# ArudinoShield.net
KiCad netlist of a schematic drawn in EAGLE
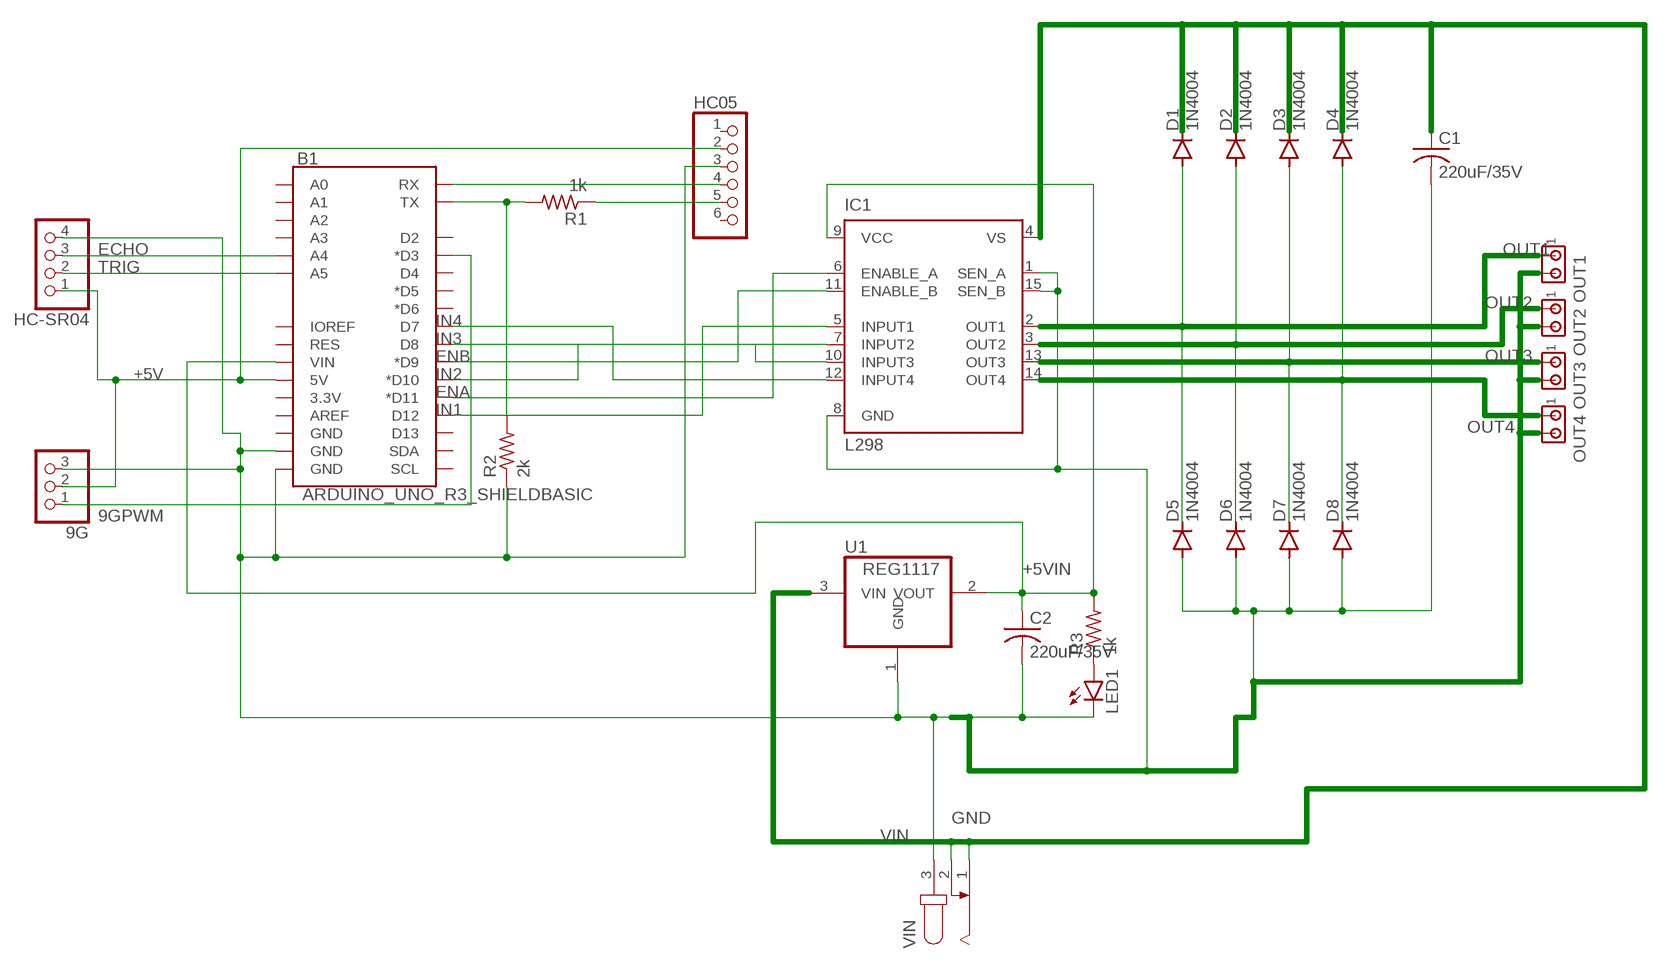
[diagram p0: schematic, sheet 1]

(export (version "E")
  (design (tool "Eeschema 10.0.6"))
  (components
    (comp (ref "9G")
      (value "PINHD-1X3")
      (footprint "eagle-import:1X03")
      (libsource (lib "eagle-import") (part "PINHD-1X3"))
    )
    (comp (ref "B1")
      (value "ARDUINO_UNO_R3_SHIELDBASIC")
      (footprint "eagle-import:UNO_R3_SHIELD")
      (libsource (lib "eagle-import") (part "ARDUINO_UNO_R3_SHIELDBASIC"))
    )
    (comp (ref "C1")
      (value "220uF/35V")
      (footprint "eagle-import:C050-024X044")
      (libsource (lib "eagle-import") (part "C-US050-024X044"))
    )
    (comp (ref "C2")
      (value "220uF/35V")
      (footprint "eagle-import:C050-024X044")
      (libsource (lib "eagle-import") (part "C-US050-024X044"))
    )
    (comp (ref "D1")
      (value "1N4004")
      (footprint "eagle-import:DO41-10")
      (libsource (lib "eagle-import") (part "1N4004"))
    )
    (comp (ref "D2")
      (value "1N4004")
      (footprint "eagle-import:DO41-10")
      (libsource (lib "eagle-import") (part "1N4004"))
    )
    (comp (ref "D3")
      (value "1N4004")
      (footprint "eagle-import:DO41-10")
      (libsource (lib "eagle-import") (part "1N4004"))
    )
    (comp (ref "D4")
      (value "1N4004")
      (footprint "eagle-import:DO41-10")
      (libsource (lib "eagle-import") (part "1N4004"))
    )
    (comp (ref "D5")
      (value "1N4004")
      (footprint "eagle-import:DO41-10")
      (libsource (lib "eagle-import") (part "1N4004"))
    )
    (comp (ref "D6")
      (value "1N4004")
      (footprint "eagle-import:DO41-10")
      (libsource (lib "eagle-import") (part "1N4004"))
    )
    (comp (ref "D7")
      (value "1N4004")
      (footprint "eagle-import:DO41-10")
      (libsource (lib "eagle-import") (part "1N4004"))
    )
    (comp (ref "D8")
      (value "1N4004")
      (footprint "eagle-import:DO41-10")
      (libsource (lib "eagle-import") (part "1N4004"))
    )
    (comp (ref "HC-SR04")
      (value "PINHD-1X4")
      (footprint "eagle-import:1X04")
      (libsource (lib "eagle-import") (part "PINHD-1X4"))
    )
    (comp (ref "HC05")
      (value "PINHD-1X6/90")
      (footprint "eagle-import:1X06_90")
      (libsource (lib "eagle-import") (part "PINHD-1X6/90"))
    )
    (comp (ref "IC1")
      (value "L298")
      (footprint "eagle-import:MULTIWATT-15")
      (fields (field (name "MPN") "L298N"))
      (libsource (lib "eagle-import") (part "L298"))
    )
    (comp (ref "LED1")
      (value "LED5MM")
      (footprint "eagle-import:LED5MM")
      (libsource (lib "eagle-import") (part "LED5MM"))
    )
    (comp (ref "OUT1")
      (value "MTA02-156")
      (footprint "eagle-import:1X2MTA")
      (libsource (lib "eagle-import") (part "MTA02-156"))
    )
    (comp (ref "OUT2")
      (value "MTA02-156")
      (footprint "eagle-import:1X2MTA")
      (libsource (lib "eagle-import") (part "MTA02-156"))
    )
    (comp (ref "OUT3")
      (value "MTA02-156")
      (footprint "eagle-import:1X2MTA")
      (libsource (lib "eagle-import") (part "MTA02-156"))
    )
    (comp (ref "OUT4")
      (value "MTA02-156")
      (footprint "eagle-import:1X2MTA")
      (libsource (lib "eagle-import") (part "MTA02-156"))
    )
    (comp (ref "R1")
      (value "1k")
      (footprint "eagle-import:0207_10")
      (libsource (lib "eagle-import") (part "R-US_0207/10"))
    )
    (comp (ref "R2")
      (value "2k")
      (footprint "eagle-import:0207_10")
      (libsource (lib "eagle-import") (part "R-US_0207/10"))
    )
    (comp (ref "R3")
      (value "1k")
      (footprint "eagle-import:0207_10")
      (libsource (lib "eagle-import") (part "R-US_0207/10"))
    )
    (comp (ref "U1")
      (value "REG1117")
      (footprint "eagle-import:SOT223")
      (libsource (lib "eagle-import") (part "REG1117"))
    )
    (comp (ref "VIN")
      (value "JACK-PLUG1")
      (footprint "eagle-import:SPC4078")
      (libsource (lib "eagle-import") (part "JACK-PLUG1"))
    )
  )
  (nets
    (net (code "1") (name "/+5V") (class "Default")
      (node (ref "9G") (pin "2") (pinfunction "2_2") (pintype "passive"))
      (node (ref "B1") (pin "5V") (pinfunction "5V_5V") (pintype "bidirectional"))
      (node (ref "HC-SR04") (pin "1") (pinfunction "1_1") (pintype "passive"))
      (node (ref "HC05") (pin "2") (pinfunction "2_2") (pintype "passive"))
    )
    (net (code "2") (name "/+5VIN") (class "Default")
      (node (ref "B1") (pin "VIN") (pinfunction "VIN_VIN") (pintype "bidirectional"))
      (node (ref "C2") (pin "1") (pinfunction "1_1") (pintype "passive"))
      (node (ref "IC1") (pin "9") (pinfunction "VCC_9") (pintype "power_in"))
      (node (ref "R3") (pin "2") (pinfunction "2_2") (pintype "passive"))
      (node (ref "U1") (pin "2") (pinfunction "VOUT_2") (pintype "output"))
    )
    (net (code "3") (name "/9GPWM") (class "Default")
      (node (ref "9G") (pin "1") (pinfunction "1_1") (pintype "passive"))
      (node (ref "B1") (pin "D3") (pinfunction "*D3_D3") (pintype "bidirectional"))
    )
    (net (code "4") (name "/ECHO") (class "Default")
      (node (ref "B1") (pin "A4") (pinfunction "A4_A4") (pintype "bidirectional"))
      (node (ref "HC-SR04") (pin "3") (pinfunction "3_3") (pintype "passive"))
    )
    (net (code "5") (name "/ENA") (class "Default")
      (node (ref "B1") (pin "D11") (pinfunction "*D11_D11") (pintype "bidirectional"))
      (node (ref "IC1") (pin "6") (pinfunction "ENABLE_A_6") (pintype "input"))
    )
    (net (code "6") (name "/ENB") (class "Default")
      (node (ref "B1") (pin "D9") (pinfunction "*D9_D9") (pintype "bidirectional"))
      (node (ref "IC1") (pin "11") (pinfunction "ENABLE_B_11") (pintype "input"))
    )
    (net (code "7") (name "/GND") (class "Default")
      (node (ref "9G") (pin "3") (pinfunction "3_3") (pintype "passive"))
      (node (ref "B1") (pin "GND@0") (pinfunction "GND_GND@0") (pintype "bidirectional"))
      (node (ref "B1") (pin "GND@1") (pinfunction "GND_GND@1") (pintype "bidirectional"))
      (node (ref "C1") (pin "2") (pinfunction "2_2") (pintype "passive"))
      (node (ref "C2") (pin "2") (pinfunction "2_2") (pintype "passive"))
      (node (ref "D5") (pin "A") (pinfunction "A_A") (pintype "passive"))
      (node (ref "D6") (pin "A") (pinfunction "A_A") (pintype "passive"))
      (node (ref "D7") (pin "A") (pinfunction "A_A") (pintype "passive"))
      (node (ref "D8") (pin "A") (pinfunction "A_A") (pintype "passive"))
      (node (ref "HC-SR04") (pin "4") (pinfunction "4_4") (pintype "passive"))
      (node (ref "HC05") (pin "3") (pinfunction "3_3") (pintype "passive"))
      (node (ref "IC1") (pin "1") (pinfunction "SEN_A_1") (pintype "input"))
      (node (ref "IC1") (pin "15") (pinfunction "SEN_B_15") (pintype "input"))
      (node (ref "IC1") (pin "8") (pinfunction "GND_8") (pintype "power_in"))
      (node (ref "LED1") (pin "K") (pinfunction "C_K") (pintype "passive"))
      (node (ref "OUT1") (pin "2") (pinfunction "2_2") (pintype "passive"))
      (node (ref "OUT2") (pin "2") (pinfunction "2_2") (pintype "passive"))
      (node (ref "OUT3") (pin "2") (pinfunction "2_2") (pintype "passive"))
      (node (ref "OUT4") (pin "2") (pinfunction "2_2") (pintype "passive"))
      (node (ref "R2") (pin "1") (pinfunction "1_1") (pintype "passive"))
      (node (ref "U1") (pin "1") (pinfunction "GND_1") (pintype "power_in"))
      (node (ref "VIN") (pin "3") (pinfunction "3_3") (pintype "passive"))
    )
    (net (code "8") (name "/IN1") (class "Default")
      (node (ref "B1") (pin "D12") (pinfunction "D12_D12") (pintype "bidirectional"))
      (node (ref "IC1") (pin "5") (pinfunction "INPUT1_5") (pintype "input"))
    )
    (net (code "9") (name "/IN2") (class "Default")
      (node (ref "B1") (pin "D10") (pinfunction "*D10_D10") (pintype "bidirectional"))
      (node (ref "IC1") (pin "7") (pinfunction "INPUT2_7") (pintype "input"))
    )
    (net (code "10") (name "/IN3") (class "Default")
      (node (ref "B1") (pin "D8") (pinfunction "D8_D8") (pintype "bidirectional"))
      (node (ref "IC1") (pin "10") (pinfunction "INPUT3_10") (pintype "input"))
    )
    (net (code "11") (name "/IN4") (class "Default")
      (node (ref "B1") (pin "D7") (pinfunction "D7_D7") (pintype "bidirectional"))
      (node (ref "IC1") (pin "12") (pinfunction "INPUT4_12") (pintype "input"))
    )
    (net (code "12") (name "/OUT1") (class "Default")
      (node (ref "D1") (pin "A") (pinfunction "A_A") (pintype "passive"))
      (node (ref "D5") (pin "C") (pinfunction "C_C") (pintype "passive"))
      (node (ref "IC1") (pin "2") (pinfunction "OUT1_2") (pintype "output"))
      (node (ref "OUT1") (pin "1") (pinfunction "1_1") (pintype "passive"))
    )
    (net (code "13") (name "/OUT2") (class "Default")
      (node (ref "D2") (pin "A") (pinfunction "A_A") (pintype "passive"))
      (node (ref "D6") (pin "C") (pinfunction "C_C") (pintype "passive"))
      (node (ref "IC1") (pin "3") (pinfunction "OUT2_3") (pintype "output"))
      (node (ref "OUT2") (pin "1") (pinfunction "1_1") (pintype "passive"))
    )
    (net (code "14") (name "/OUT3") (class "Default")
      (node (ref "D3") (pin "A") (pinfunction "A_A") (pintype "passive"))
      (node (ref "D7") (pin "C") (pinfunction "C_C") (pintype "passive"))
      (node (ref "IC1") (pin "13") (pinfunction "OUT3_13") (pintype "output"))
      (node (ref "OUT3") (pin "1") (pinfunction "1_1") (pintype "passive"))
    )
    (net (code "15") (name "/OUT4") (class "Default")
      (node (ref "D4") (pin "A") (pinfunction "A_A") (pintype "passive"))
      (node (ref "D8") (pin "C") (pinfunction "C_C") (pintype "passive"))
      (node (ref "IC1") (pin "14") (pinfunction "OUT4_14") (pintype "output"))
      (node (ref "OUT4") (pin "1") (pinfunction "1_1") (pintype "passive"))
    )
    (net (code "16") (name "/TRIG") (class "Default")
      (node (ref "B1") (pin "A5") (pinfunction "A5_A5") (pintype "bidirectional"))
      (node (ref "HC-SR04") (pin "2") (pinfunction "2_2") (pintype "passive"))
    )
    (net (code "17") (name "/VIN") (class "Default")
      (node (ref "C1") (pin "1") (pinfunction "1_1") (pintype "passive"))
      (node (ref "D1") (pin "C") (pinfunction "C_C") (pintype "passive"))
      (node (ref "D2") (pin "C") (pinfunction "C_C") (pintype "passive"))
      (node (ref "D3") (pin "C") (pinfunction "C_C") (pintype "passive"))
      (node (ref "D4") (pin "C") (pinfunction "C_C") (pintype "passive"))
      (node (ref "IC1") (pin "4") (pinfunction "VS_4") (pintype "power_in"))
      (node (ref "U1") (pin "3") (pinfunction "VIN_3") (pintype "input"))
      (node (ref "VIN") (pin "1") (pinfunction "1_1") (pintype "passive"))
      (node (ref "VIN") (pin "2") (pinfunction "2_2") (pintype "passive"))
    )
    (net (code "18") (name "Net-(B1-PadRX)") (class "Default")
      (node (ref "B1") (pin "RX") (pinfunction "RX_RX") (pintype "bidirectional"))
      (node (ref "HC05") (pin "4") (pinfunction "4_4") (pintype "passive"))
    )
    (net (code "19") (name "Net-(B1-PadTX)") (class "Default")
      (node (ref "B1") (pin "TX") (pinfunction "TX_TX") (pintype "bidirectional"))
      (node (ref "R1") (pin "2") (pinfunction "2_2") (pintype "passive"))
      (node (ref "R2") (pin "2") (pinfunction "2_2") (pintype "passive"))
    )
    (net (code "20") (name "Net-(HC05-Pad5)") (class "Default")
      (node (ref "HC05") (pin "5") (pinfunction "5_5") (pintype "passive"))
      (node (ref "R1") (pin "1") (pinfunction "1_1") (pintype "passive"))
    )
    (net (code "21") (name "Net-(LED1-PadA)") (class "Default")
      (node (ref "LED1") (pin "A") (pinfunction "A_A") (pintype "passive"))
      (node (ref "R3") (pin "1") (pinfunction "1_1") (pintype "passive"))
    )
    (net (code "22") (name "unconnected-(B1-*D5-PadD5)") (class "Default")
      (node (ref "B1") (pin "D5") (pinfunction "*D5_D5") (pintype "bidirectional"))
    )
    (net (code "23") (name "unconnected-(B1-*D6-PadD6)") (class "Default")
      (node (ref "B1") (pin "D6") (pinfunction "*D6_D6") (pintype "bidirectional"))
    )
    (net (code "24") (name "unconnected-(B1-GND-PadGND@2)") (class "Default")
      (node (ref "B1") (pin "GND@2") (pinfunction "GND_GND@2") (pintype "bidirectional"))
    )
    (net (code "25") (name "unconnected-(B1-Pad3.3V)") (class "Default")
      (node (ref "B1") (pin "3.3V") (pinfunction "3.3V_3.3V") (pintype "bidirectional"))
    )
    (net (code "26") (name "unconnected-(B1-PadA0)") (class "Default")
      (node (ref "B1") (pin "A0") (pinfunction "A0_A0") (pintype "bidirectional"))
    )
    (net (code "27") (name "unconnected-(B1-PadA1)") (class "Default")
      (node (ref "B1") (pin "A1") (pinfunction "A1_A1") (pintype "bidirectional"))
    )
    (net (code "28") (name "unconnected-(B1-PadA2)") (class "Default")
      (node (ref "B1") (pin "A2") (pinfunction "A2_A2") (pintype "bidirectional"))
    )
    (net (code "29") (name "unconnected-(B1-PadA3)") (class "Default")
      (node (ref "B1") (pin "A3") (pinfunction "A3_A3") (pintype "bidirectional"))
    )
    (net (code "30") (name "unconnected-(B1-PadAREF)") (class "Default")
      (node (ref "B1") (pin "AREF") (pinfunction "AREF_AREF") (pintype "bidirectional"))
    )
    (net (code "31") (name "unconnected-(B1-PadD2)") (class "Default")
      (node (ref "B1") (pin "D2") (pinfunction "D2_D2") (pintype "bidirectional"))
    )
    (net (code "32") (name "unconnected-(B1-PadD4)") (class "Default")
      (node (ref "B1") (pin "D4") (pinfunction "D4_D4") (pintype "bidirectional"))
    )
    (net (code "33") (name "unconnected-(B1-PadD13)") (class "Default")
      (node (ref "B1") (pin "D13") (pinfunction "D13_D13") (pintype "bidirectional"))
    )
    (net (code "34") (name "unconnected-(B1-PadIOREF)") (class "Default")
      (node (ref "B1") (pin "IOREF") (pinfunction "IOREF_IOREF") (pintype "bidirectional"))
    )
    (net (code "35") (name "unconnected-(B1-PadRES)") (class "Default")
      (node (ref "B1") (pin "RES") (pinfunction "RES_RES") (pintype "bidirectional"))
    )
    (net (code "36") (name "unconnected-(B1-PadSCL)") (class "Default")
      (node (ref "B1") (pin "SCL") (pinfunction "SCL_SCL") (pintype "bidirectional"))
    )
    (net (code "37") (name "unconnected-(B1-PadSDA)") (class "Default")
      (node (ref "B1") (pin "SDA") (pinfunction "SDA_SDA") (pintype "bidirectional"))
    )
    (net (code "38") (name "unconnected-(HC05-Pad1)") (class "Default")
      (node (ref "HC05") (pin "1") (pinfunction "1_1") (pintype "passive"))
    )
    (net (code "39") (name "unconnected-(HC05-Pad6)") (class "Default")
      (node (ref "HC05") (pin "6") (pinfunction "6_6") (pintype "passive"))
    )
  )
)
